# USB_data.net
KiCad netlist of a schematic drawn in Altium Designer
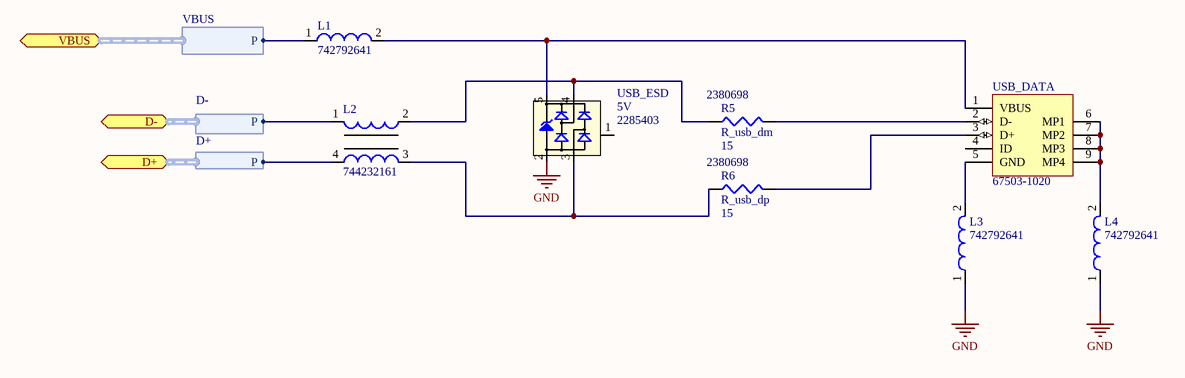
[diagram p0: USB_data.SchDoc]

(export (version "E")
  (design (tool "Eeschema 10.0.6"))
  (components
    (comp (ref "L1")
      (value "742792641")
      (footprint "SMD-0603")
      (description "SMD EMI Suppression Ferrite Bead WE-CBF, Z = 300 Ohm")
      (libsource (lib "Altium Content Vault") (part "PAS-IND-INDUCTOR-2"))
    )
    (comp (ref "L2")
      (value "744232161")
      (footprint "WE-CNSW-1206")
      (description "SMD Common Mode Noise Suppressor WE-CNSW, Z = 160 Ohm")
      (libsource (lib "Altium Content Vault") (part "CMP-0222-00033-1"))
    )
    (comp (ref "L3")
      (value "742792641")
      (footprint "SMD-0603")
      (description "SMD EMI Suppression Ferrite Bead WE-CBF, Z = 300 Ohm")
      (libsource (lib "Altium Content Vault") (part "PAS-IND-INDUCTOR-2"))
    )
    (comp (ref "L4")
      (value "742792641")
      (footprint "SMD-0603")
      (description "SMD EMI Suppression Ferrite Bead WE-CBF, Z = 300 Ohm")
      (libsource (lib "Altium Content Vault") (part "PAS-IND-INDUCTOR-2"))
    )
    (comp (ref "R5")
      (value "R_usb_dm")
      (footprint "14-1210")
      (description "Resistor")
      (fields
        (field (name "ALTIUM_VALUE") "15")
        (field (name "SUPPLIER PART NUMBER 1") "2380698")
        (field (name "MANUFACTURER") "PANASONIC")
        (field (name "MANUFACTURER PART NUMBER") "ERJU14F15R0U")
        (field (name "PUBLISHER") "Altium Limited")
      )
      (libsource (lib "Miscellaneous Devices") (part "Res3"))
    )
    (comp (ref "R6")
      (value "R_usb_dp")
      (footprint "14-1210")
      (description "Resistor")
      (fields
        (field (name "ALTIUM_VALUE") "15")
        (field (name "SUPPLIER PART NUMBER 1") "2380698")
        (field (name "MANUFACTURER") "PANASONIC")
        (field (name "MANUFACTURER PART NUMBER") "ERJU14F15R0U")
        (field (name "PUBLISHER") "Altium Limited")
      )
      (libsource (lib "Miscellaneous Devices") (part "Res3"))
    )
    (comp (ref "USB_DATA")
      (value "67503-1020")
      (footprint "MOLX-67503-1020_V")
      (description "USB, MINI, SMD, RA KME04-USBMU03A01")
      (fields (field (name "MANUFACTURER") "Molex"))
      (libsource (lib "Altium Content Vault") (part "CMP-0411-00002-1"))
    )
    (comp (ref "USB_ESD")
      (value "5V")
      (footprint "SOT95P275X140-5N")
      (description "TVS Diode WE-TVS-HS, VRWM=5V")
      (fields
        (field (name "PARTNO") "824011")
        (field (name "MANUFACTURER") "Würth Elektronik eiSos GmbH")
        (field (name "SUPPLIER PART NUMBER 1") "2285403")
        (field (name "CREATED BY") "Christin Zierenner")
      )
      (libsource (lib "WE-TVS") (part "WE-TVS-HS,SOT23-5L,824011"))
    )
  )
  (nets
    (net (code "7") (name "GND") (class "Default")
      (node (ref "L3") (pin "1") (pinfunction "1_1") (pintype "passive"))
      (node (ref "L4") (pin "1") (pinfunction "1_1") (pintype "passive"))
      (node (ref "USB_ESD") (pin "2") (pinfunction "GND_2") (pintype "passive"))
    )
    (net (code "8") (name "Net-(USB_DATA-D+)") (class "Default")
      (node (ref "R6") (pin "2") (pinfunction "2_2") (pintype "passive"))
      (node (ref "USB_DATA") (pin "3") (pinfunction "D+_3") (pintype "bidirectional"))
    )
    (net (code "9") (name "Net-(USB_DATA-D-)") (class "Default")
      (node (ref "R5") (pin "2") (pinfunction "2_2") (pintype "passive"))
      (node (ref "USB_DATA") (pin "2") (pinfunction "D-_2") (pintype "bidirectional"))
    )
    (net (code "10") (name "Net-(USB_DATA-GND)") (class "Default")
      (node (ref "L3") (pin "2") (pinfunction "2_2") (pintype "passive"))
      (node (ref "USB_DATA") (pin "5") (pinfunction "GND_5") (pintype "power_in"))
    )
    (net (code "11") (name "Net-(USB_DATA-MP1)") (class "Default")
      (node (ref "L4") (pin "2") (pinfunction "2_2") (pintype "passive"))
      (node (ref "USB_DATA") (pin "6") (pinfunction "MP1_6") (pintype "passive"))
      (node (ref "USB_DATA") (pin "7") (pinfunction "MP2_7") (pintype "passive"))
      (node (ref "USB_DATA") (pin "8") (pinfunction "MP3_8") (pintype "passive"))
      (node (ref "USB_DATA") (pin "9") (pinfunction "MP4_9") (pintype "passive"))
    )
    (net (code "12") (name "Net-(USB_DATA-VBUS)") (class "Default")
      (node (ref "L1") (pin "2") (pinfunction "2_2") (pintype "passive"))
      (node (ref "USB_DATA") (pin "1") (pinfunction "VBUS_1") (pintype "power_in"))
      (node (ref "USB_ESD") (pin "5") (pinfunction "VDD_5") (pintype "passive"))
    )
    (net (code "13") (name "Net-(USB_ESD-I{slash}O1)") (class "Default")
      (node (ref "L2") (pin "3") (pinfunction "3_3") (pintype "passive"))
      (node (ref "R6") (pin "1") (pinfunction "1_1") (pintype "passive"))
      (node (ref "USB_ESD") (pin "3") (pinfunction "I/O1_3") (pintype "passive"))
    )
    (net (code "14") (name "Net-(USB_ESD-I{slash}O2)") (class "Default")
      (node (ref "L2") (pin "2") (pinfunction "2_2") (pintype "passive"))
      (node (ref "R5") (pin "1") (pinfunction "1_1") (pintype "passive"))
      (node (ref "USB_ESD") (pin "4") (pinfunction "I/O2_4") (pintype "passive"))
    )
    (net (code "15") (name "unconnected-(L1-Pad1)") (class "Default")
      (node (ref "L1") (pin "1") (pinfunction "1_1") (pintype "passive"))
    )
    (net (code "16") (name "unconnected-(L2-Pad1)") (class "Default")
      (node (ref "L2") (pin "1") (pinfunction "1_1") (pintype "passive"))
    )
    (net (code "17") (name "unconnected-(L2-Pad4)") (class "Default")
      (node (ref "L2") (pin "4") (pinfunction "4_4") (pintype "passive"))
    )
    (net (code "18") (name "unconnected-(USB_DATA-ID-Pad4)") (class "Default")
      (node (ref "USB_DATA") (pin "4") (pinfunction "ID_4") (pintype "passive"))
    )
    (net (code "19") (name "unconnected-(USB_ESD-NC-Pad1)") (class "Default")
      (node (ref "USB_ESD") (pin "1") (pinfunction "NC_1") (pintype "passive"))
    )
  )
)
